# USB_Hub.net
KiCad netlist of a schematic drawn in Altium Designer
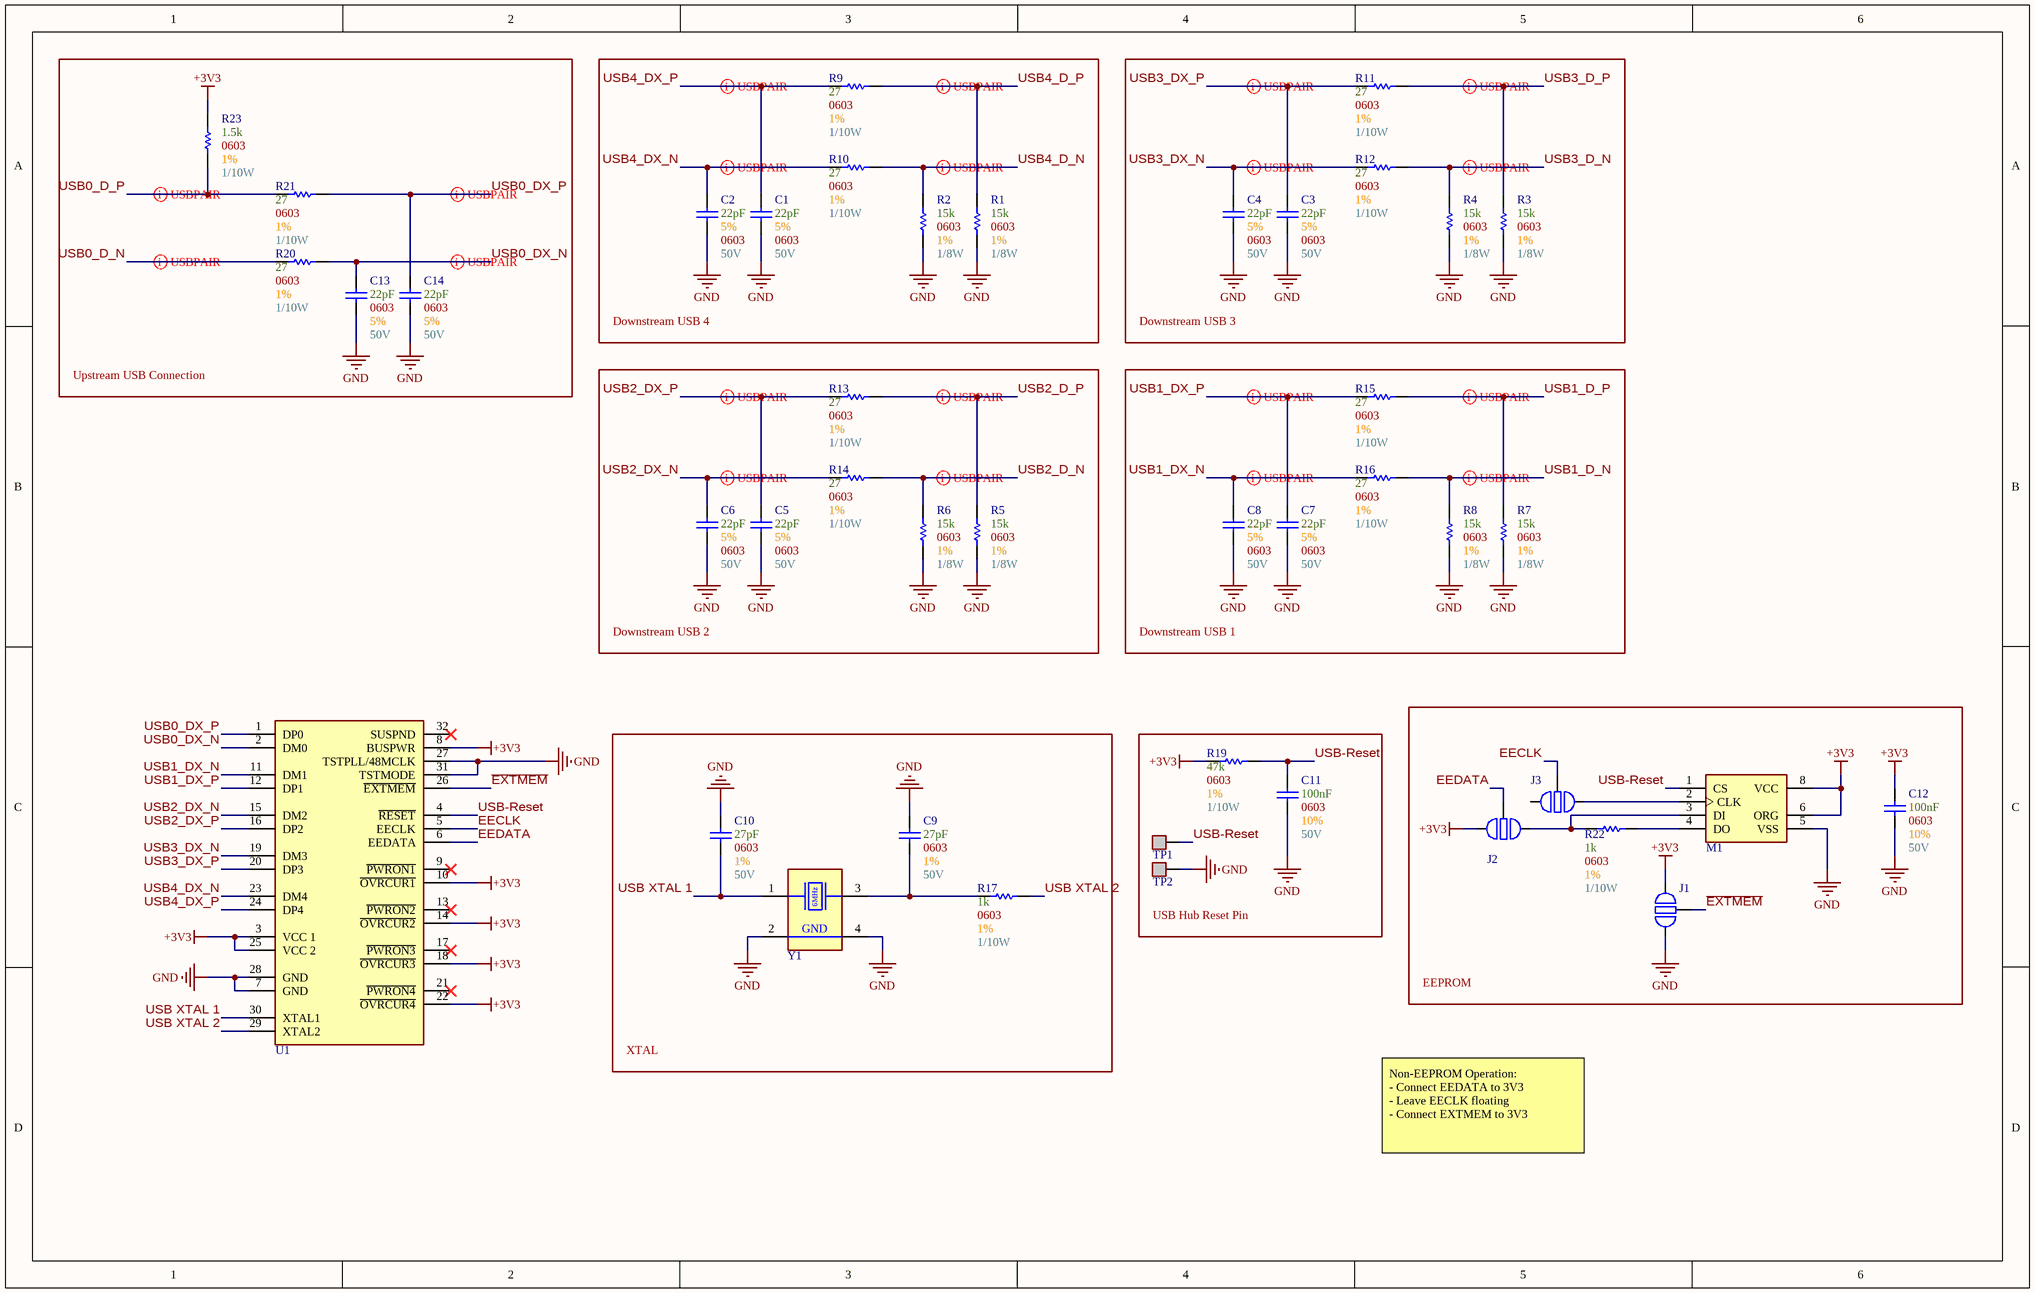
[diagram p0: USB Hub.SchDoc]

(export (version "E")
  (design (tool "Eeschema 10.0.6"))
  (components
    (comp (ref "C1")
      (value "[Cap] 0603 22pF 5% 50V")
      (footprint "[Cap] SMD 0603")
      (description "CC0603JRNPO9BN240")
      (fields
        (field (name "MAX VOLTAGE") "50V")
        (field (name "SIZE PACKAGE") "0603")
        (field (name "TOLERANCE") "5%")
        (field (name "CAPACITANCE") "22pF")
      )
      (libsource (lib "Capacitors") (part "[Cap] 0603 22pF 5% 50V"))
    )
    (comp (ref "C2")
      (value "[Cap] 0603 22pF 5% 50V")
      (footprint "[Cap] SMD 0603")
      (description "CC0603JRNPO9BN240")
      (fields
        (field (name "MAX VOLTAGE") "50V")
        (field (name "SIZE PACKAGE") "0603")
        (field (name "TOLERANCE") "5%")
        (field (name "CAPACITANCE") "22pF")
      )
      (libsource (lib "Capacitors") (part "[Cap] 0603 22pF 5% 50V"))
    )
    (comp (ref "C3")
      (value "[Cap] 0603 22pF 5% 50V")
      (footprint "[Cap] SMD 0603")
      (description "CC0603JRNPO9BN240")
      (fields
        (field (name "MAX VOLTAGE") "50V")
        (field (name "SIZE PACKAGE") "0603")
        (field (name "TOLERANCE") "5%")
        (field (name "CAPACITANCE") "22pF")
      )
      (libsource (lib "Capacitors") (part "[Cap] 0603 22pF 5% 50V"))
    )
    (comp (ref "C4")
      (value "[Cap] 0603 22pF 5% 50V")
      (footprint "[Cap] SMD 0603")
      (description "CC0603JRNPO9BN240")
      (fields
        (field (name "MAX VOLTAGE") "50V")
        (field (name "SIZE PACKAGE") "0603")
        (field (name "TOLERANCE") "5%")
        (field (name "CAPACITANCE") "22pF")
      )
      (libsource (lib "Capacitors") (part "[Cap] 0603 22pF 5% 50V"))
    )
    (comp (ref "C5")
      (value "[Cap] 0603 22pF 5% 50V")
      (footprint "[Cap] SMD 0603")
      (description "CC0603JRNPO9BN240")
      (fields
        (field (name "MAX VOLTAGE") "50V")
        (field (name "SIZE PACKAGE") "0603")
        (field (name "TOLERANCE") "5%")
        (field (name "CAPACITANCE") "22pF")
      )
      (libsource (lib "Capacitors") (part "[Cap] 0603 22pF 5% 50V"))
    )
    (comp (ref "C6")
      (value "[Cap] 0603 22pF 5% 50V")
      (footprint "[Cap] SMD 0603")
      (description "CC0603JRNPO9BN240")
      (fields
        (field (name "MAX VOLTAGE") "50V")
        (field (name "SIZE PACKAGE") "0603")
        (field (name "TOLERANCE") "5%")
        (field (name "CAPACITANCE") "22pF")
      )
      (libsource (lib "Capacitors") (part "[Cap] 0603 22pF 5% 50V"))
    )
    (comp (ref "C7")
      (value "[Cap] 0603 22pF 5% 50V")
      (footprint "[Cap] SMD 0603")
      (description "CC0603JRNPO9BN240")
      (fields
        (field (name "MAX VOLTAGE") "50V")
        (field (name "SIZE PACKAGE") "0603")
        (field (name "TOLERANCE") "5%")
        (field (name "CAPACITANCE") "22pF")
      )
      (libsource (lib "Capacitors") (part "[Cap] 0603 22pF 5% 50V"))
    )
    (comp (ref "C8")
      (value "[Cap] 0603 22pF 5% 50V")
      (footprint "[Cap] SMD 0603")
      (description "CC0603JRNPO9BN240")
      (fields
        (field (name "MAX VOLTAGE") "50V")
        (field (name "SIZE PACKAGE") "0603")
        (field (name "TOLERANCE") "5%")
        (field (name "CAPACITANCE") "22pF")
      )
      (libsource (lib "Capacitors") (part "[Cap] 0603 22pF 5% 50V"))
    )
    (comp (ref "C9")
      (value "[Cap] 0603 27pF 1% 50V")
      (footprint "[Cap] SMD 0603")
      (description "0603N270F500CT")
      (fields
        (field (name "MAX VOLTAGE") "50V")
        (field (name "SIZE PACKAGE") "0603")
        (field (name "TOLERANCE") "1%")
        (field (name "CAPACITANCE") "27pF")
      )
      (libsource (lib "Capacitors") (part "[Cap] 0603 27pF 1% 50V"))
    )
    (comp (ref "C10")
      (value "[Cap] 0603 27pF 1% 50V")
      (footprint "[Cap] SMD 0603")
      (description "0603N270F500CT")
      (fields
        (field (name "MAX VOLTAGE") "50V")
        (field (name "SIZE PACKAGE") "0603")
        (field (name "TOLERANCE") "1%")
        (field (name "CAPACITANCE") "27pF")
      )
      (libsource (lib "Capacitors") (part "[Cap] 0603 27pF 1% 50V"))
    )
    (comp (ref "C11")
      (value "[Cap] 0603 0.1uF 10% 50V")
      (footprint "[Cap] SMD 0603")
      (description "CL10B104KB8NNNC")
      (fields
        (field (name "MAX VOLTAGE") "50V")
        (field (name "SIZE PACKAGE") "0603")
        (field (name "TOLERANCE") "10%")
        (field (name "CAPACITANCE") "100nF")
      )
      (libsource (lib "Capacitors") (part "[Cap] 0603 0.1uF 10% 50V"))
    )
    (comp (ref "C12")
      (value "[Cap] 0603 0.1uF 10% 50V")
      (footprint "[Cap] SMD 0603")
      (description "CL10B104KB8NNNC")
      (fields
        (field (name "MAX VOLTAGE") "50V")
        (field (name "SIZE PACKAGE") "0603")
        (field (name "TOLERANCE") "10%")
        (field (name "CAPACITANCE") "100nF")
      )
      (libsource (lib "Capacitors") (part "[Cap] 0603 0.1uF 10% 50V"))
    )
    (comp (ref "C13")
      (value "[Cap] 0603 22pF 5% 50V")
      (footprint "[Cap] SMD 0603")
      (description "CC0603JRNPO9BN240")
      (fields
        (field (name "MAX VOLTAGE") "50V")
        (field (name "SIZE PACKAGE") "0603")
        (field (name "TOLERANCE") "5%")
        (field (name "CAPACITANCE") "22pF")
      )
      (libsource (lib "Capacitors") (part "[Cap] 0603 22pF 5% 50V"))
    )
    (comp (ref "C14")
      (value "[Cap] 0603 22pF 5% 50V")
      (footprint "[Cap] SMD 0603")
      (description "CC0603JRNPO9BN240")
      (fields
        (field (name "MAX VOLTAGE") "50V")
        (field (name "SIZE PACKAGE") "0603")
        (field (name "TOLERANCE") "5%")
        (field (name "CAPACITANCE") "22pF")
      )
      (libsource (lib "Capacitors") (part "[Cap] 0603 22pF 5% 50V"))
    )
    (comp (ref "J1")
      (value "[Jumper] Thru-Hole 3pin")
      (footprint "[Jumper] Thru-Hole 3pin")
      (libsource (lib "Misc Components") (part "[Jumper] Thru-Hole 3pin"))
    )
    (comp (ref "J2")
      (value "[Jumper] Thru-Hole 3pin")
      (footprint "[Jumper] Thru-Hole 3pin")
      (libsource (lib "Misc Components") (part "[Jumper] Thru-Hole 3pin"))
    )
    (comp (ref "J3")
      (value "[Jumper] Thru-Hole 3pin")
      (footprint "[Jumper] Thru-Hole 3pin")
      (libsource (lib "Misc Components") (part "[Jumper] Thru-Hole 3pin"))
    )
    (comp (ref "M1")
      (value "[Flash] 32x16b")
      (footprint "[Flash] 32x16b")
      (description "M93C46-WMN6TP")
      (libsource (lib "Memory") (part "[Flash] 32x16b"))
    )
    (comp (ref "R1")
      (value "[15k] SMD 0603 1% 1/8W")
      (footprint "[Res] SMD 0603")
      (description "CRCW060315K0FKEA")
      (fields
        (field (name "WATTAGE") "1/8W")
        (field (name "TOLERANCE") "1%")
        (field (name "RESISTANCE") "15k")
        (field (name "SIZE PACKAGE") "0603")
      )
      (libsource (lib "Resistors") (part "[15k] SMD 0603 1% 1/8W"))
    )
    (comp (ref "R2")
      (value "[15k] SMD 0603 1% 1/8W")
      (footprint "[Res] SMD 0603")
      (description "CRCW060315K0FKEA")
      (fields
        (field (name "WATTAGE") "1/8W")
        (field (name "TOLERANCE") "1%")
        (field (name "RESISTANCE") "15k")
        (field (name "SIZE PACKAGE") "0603")
      )
      (libsource (lib "Resistors") (part "[15k] SMD 0603 1% 1/8W"))
    )
    (comp (ref "R3")
      (value "[15k] SMD 0603 1% 1/8W")
      (footprint "[Res] SMD 0603")
      (description "CRCW060315K0FKEA")
      (fields
        (field (name "WATTAGE") "1/8W")
        (field (name "TOLERANCE") "1%")
        (field (name "RESISTANCE") "15k")
        (field (name "SIZE PACKAGE") "0603")
      )
      (libsource (lib "Resistors") (part "[15k] SMD 0603 1% 1/8W"))
    )
    (comp (ref "R4")
      (value "[15k] SMD 0603 1% 1/8W")
      (footprint "[Res] SMD 0603")
      (description "CRCW060315K0FKEA")
      (fields
        (field (name "WATTAGE") "1/8W")
        (field (name "TOLERANCE") "1%")
        (field (name "RESISTANCE") "15k")
        (field (name "SIZE PACKAGE") "0603")
      )
      (libsource (lib "Resistors") (part "[15k] SMD 0603 1% 1/8W"))
    )
    (comp (ref "R5")
      (value "[15k] SMD 0603 1% 1/8W")
      (footprint "[Res] SMD 0603")
      (description "CRCW060315K0FKEA")
      (fields
        (field (name "WATTAGE") "1/8W")
        (field (name "TOLERANCE") "1%")
        (field (name "RESISTANCE") "15k")
        (field (name "SIZE PACKAGE") "0603")
      )
      (libsource (lib "Resistors") (part "[15k] SMD 0603 1% 1/8W"))
    )
    (comp (ref "R6")
      (value "[15k] SMD 0603 1% 1/8W")
      (footprint "[Res] SMD 0603")
      (description "CRCW060315K0FKEA")
      (fields
        (field (name "WATTAGE") "1/8W")
        (field (name "TOLERANCE") "1%")
        (field (name "RESISTANCE") "15k")
        (field (name "SIZE PACKAGE") "0603")
      )
      (libsource (lib "Resistors") (part "[15k] SMD 0603 1% 1/8W"))
    )
    (comp (ref "R7")
      (value "[15k] SMD 0603 1% 1/8W")
      (footprint "[Res] SMD 0603")
      (description "CRCW060315K0FKEA")
      (fields
        (field (name "WATTAGE") "1/8W")
        (field (name "TOLERANCE") "1%")
        (field (name "RESISTANCE") "15k")
        (field (name "SIZE PACKAGE") "0603")
      )
      (libsource (lib "Resistors") (part "[15k] SMD 0603 1% 1/8W"))
    )
    (comp (ref "R8")
      (value "[15k] SMD 0603 1% 1/8W")
      (footprint "[Res] SMD 0603")
      (description "CRCW060315K0FKEA")
      (fields
        (field (name "WATTAGE") "1/8W")
        (field (name "TOLERANCE") "1%")
        (field (name "RESISTANCE") "15k")
        (field (name "SIZE PACKAGE") "0603")
      )
      (libsource (lib "Resistors") (part "[15k] SMD 0603 1% 1/8W"))
    )
    (comp (ref "R9")
      (value "[27] SMD 0603 1% 1/10W")
      (footprint "[Res] SMD 0603")
      (description "MCT06030C2709FP500")
      (fields
        (field (name "WATTAGE") "1/10W")
        (field (name "TOLERANCE") "1%")
        (field (name "RESISTANCE") "27")
        (field (name "SIZE PACKAGE") "0603")
      )
      (libsource (lib "Resistors") (part "[27] SMD 0603 1% 1/10W"))
    )
    (comp (ref "R10")
      (value "[27] SMD 0603 1% 1/10W")
      (footprint "[Res] SMD 0603")
      (description "MCT06030C2709FP500")
      (fields
        (field (name "WATTAGE") "1/10W")
        (field (name "TOLERANCE") "1%")
        (field (name "RESISTANCE") "27")
        (field (name "SIZE PACKAGE") "0603")
      )
      (libsource (lib "Resistors") (part "[27] SMD 0603 1% 1/10W"))
    )
    (comp (ref "R11")
      (value "[27] SMD 0603 1% 1/10W")
      (footprint "[Res] SMD 0603")
      (description "MCT06030C2709FP500")
      (fields
        (field (name "WATTAGE") "1/10W")
        (field (name "TOLERANCE") "1%")
        (field (name "RESISTANCE") "27")
        (field (name "SIZE PACKAGE") "0603")
      )
      (libsource (lib "Resistors") (part "[27] SMD 0603 1% 1/10W"))
    )
    (comp (ref "R12")
      (value "[27] SMD 0603 1% 1/10W")
      (footprint "[Res] SMD 0603")
      (description "MCT06030C2709FP500")
      (fields
        (field (name "WATTAGE") "1/10W")
        (field (name "TOLERANCE") "1%")
        (field (name "RESISTANCE") "27")
        (field (name "SIZE PACKAGE") "0603")
      )
      (libsource (lib "Resistors") (part "[27] SMD 0603 1% 1/10W"))
    )
    (comp (ref "R13")
      (value "[27] SMD 0603 1% 1/10W")
      (footprint "[Res] SMD 0603")
      (description "MCT06030C2709FP500")
      (fields
        (field (name "WATTAGE") "1/10W")
        (field (name "TOLERANCE") "1%")
        (field (name "RESISTANCE") "27")
        (field (name "SIZE PACKAGE") "0603")
      )
      (libsource (lib "Resistors") (part "[27] SMD 0603 1% 1/10W"))
    )
    (comp (ref "R14")
      (value "[27] SMD 0603 1% 1/10W")
      (footprint "[Res] SMD 0603")
      (description "MCT06030C2709FP500")
      (fields
        (field (name "WATTAGE") "1/10W")
        (field (name "TOLERANCE") "1%")
        (field (name "RESISTANCE") "27")
        (field (name "SIZE PACKAGE") "0603")
      )
      (libsource (lib "Resistors") (part "[27] SMD 0603 1% 1/10W"))
    )
    (comp (ref "R15")
      (value "[27] SMD 0603 1% 1/10W")
      (footprint "[Res] SMD 0603")
      (description "MCT06030C2709FP500")
      (fields
        (field (name "WATTAGE") "1/10W")
        (field (name "TOLERANCE") "1%")
        (field (name "RESISTANCE") "27")
        (field (name "SIZE PACKAGE") "0603")
      )
      (libsource (lib "Resistors") (part "[27] SMD 0603 1% 1/10W"))
    )
    (comp (ref "R16")
      (value "[27] SMD 0603 1% 1/10W")
      (footprint "[Res] SMD 0603")
      (description "MCT06030C2709FP500")
      (fields
        (field (name "WATTAGE") "1/10W")
        (field (name "TOLERANCE") "1%")
        (field (name "RESISTANCE") "27")
        (field (name "SIZE PACKAGE") "0603")
      )
      (libsource (lib "Resistors") (part "[27] SMD 0603 1% 1/10W"))
    )
    (comp (ref "R17")
      (value "[1k] SMD 0603 1% 1/10W")
      (footprint "[Res] SMD 0603")
      (description "RMCF0603FT1K00")
      (fields
        (field (name "WATTAGE") "1/10W")
        (field (name "TOLERANCE") "1%")
        (field (name "RESISTANCE") "1k")
        (field (name "SIZE PACKAGE") "0603")
      )
      (libsource (lib "Resistors") (part "[1k] SMD 0603 1% 1/10W"))
    )
    (comp (ref "R19")
      (value "[47k] SMD 0603 1% 1/10W")
      (footprint "[Res] SMD 0603")
      (description "RC0603FR-0747KL")
      (fields
        (field (name "WATTAGE") "1/10W")
        (field (name "TOLERANCE") "1%")
        (field (name "RESISTANCE") "47k")
        (field (name "SIZE PACKAGE") "0603")
      )
      (libsource (lib "Resistors") (part "[47k] SMD 0603 1% 1/10W"))
    )
    (comp (ref "R20")
      (value "[27] SMD 0603 1% 1/10W")
      (footprint "[Res] SMD 0603")
      (description "MCT06030C2709FP500")
      (fields
        (field (name "WATTAGE") "1/10W")
        (field (name "TOLERANCE") "1%")
        (field (name "RESISTANCE") "27")
        (field (name "SIZE PACKAGE") "0603")
      )
      (libsource (lib "Resistors") (part "[27] SMD 0603 1% 1/10W"))
    )
    (comp (ref "R21")
      (value "[27] SMD 0603 1% 1/10W")
      (footprint "[Res] SMD 0603")
      (description "MCT06030C2709FP500")
      (fields
        (field (name "WATTAGE") "1/10W")
        (field (name "TOLERANCE") "1%")
        (field (name "RESISTANCE") "27")
        (field (name "SIZE PACKAGE") "0603")
      )
      (libsource (lib "Resistors") (part "[27] SMD 0603 1% 1/10W"))
    )
    (comp (ref "R22")
      (value "[1k] SMD 0603 1% 1/10W")
      (footprint "[Res] SMD 0603")
      (description "RMCF0603FT1K00")
      (fields
        (field (name "WATTAGE") "1/10W")
        (field (name "TOLERANCE") "1%")
        (field (name "RESISTANCE") "1k")
        (field (name "SIZE PACKAGE") "0603")
      )
      (libsource (lib "Resistors") (part "[1k] SMD 0603 1% 1/10W"))
    )
    (comp (ref "R23")
      (value "[1.5k] SMD 0603 1% 1/10W")
      (footprint "[Res] SMD 0603")
      (description "CR0603-FX-1501ELF")
      (fields
        (field (name "WATTAGE") "1/10W")
        (field (name "TOLERANCE") "1%")
        (field (name "RESISTANCE") "1.5k")
        (field (name "SIZE PACKAGE") "0603")
      )
      (libsource (lib "Resistors") (part "[1.5k] SMD 0603 1% 1/10W"))
    )
    (comp (ref "TP1")
      (value "[THM] Thru-Hole")
      (footprint "[THM] White")
      (description "5012")
      (libsource (lib "Test Points") (part "[THM] Thru-Hole"))
    )
    (comp (ref "TP2")
      (value "[THM] Thru-Hole")
      (footprint "[THM] White")
      (description "5012")
      (libsource (lib "Test Points") (part "[THM] Thru-Hole"))
    )
    (comp (ref "U1")
      (value "4port")
      (footprint "[USB Hub] USB2.0 4port")
      (description "TUSB2046BVFR")
      (libsource (lib "ICs") (part "[USB Hub] USB 2.0 4port"))
    )
    (comp (ref "Y1")
      (value "[Crystal] SMD 6MHz")
      (footprint "[Crystal] SMD 6MHz")
      (description "ECS-060-18-20BM-JEN-TR")
      (libsource (lib "Crystals and Oscillators") (part "[Crystal] SMD 6MHz"))
    )
  )
  (nets
    (net (code "1") (name "+3V3") (class "Default")
      (node (ref "C12") (pin "2") (pinfunction "2_2") (pintype "passive"))
      (node (ref "J1") (pin "3") (pintype "passive"))
      (node (ref "J2") (pin "3") (pintype "passive"))
      (node (ref "M1") (pin "6") (pinfunction "ORG_6") (pintype "passive"))
      (node (ref "M1") (pin "8") (pinfunction "VCC_8") (pintype "passive"))
      (node (ref "R19") (pin "1") (pinfunction "1_1") (pintype "passive"))
      (node (ref "R23") (pin "2") (pinfunction "2_2") (pintype "passive"))
      (node (ref "U1") (pin "10") (pinfunction "~{OVRCUR1}_10") (pintype "passive"))
      (node (ref "U1") (pin "14") (pinfunction "~{OVRCUR2}_14") (pintype "passive"))
      (node (ref "U1") (pin "18") (pinfunction "~{OVRCUR3}_18") (pintype "passive"))
      (node (ref "U1") (pin "22") (pinfunction "~{OVRCUR4}_22") (pintype "passive"))
      (node (ref "U1") (pin "25") (pinfunction "VCC_2_25") (pintype "passive"))
      (node (ref "U1") (pin "3") (pinfunction "VCC_1_3") (pintype "passive"))
      (node (ref "U1") (pin "8") (pinfunction "BUSPWR_8") (pintype "passive"))
    )
    (net (code "2") (name "/EECLK") (class "Default")
      (node (ref "J3") (pin "2") (pinfunction "Common_2") (pintype "power_in"))
      (node (ref "U1") (pin "5") (pinfunction "EECLK_5") (pintype "passive"))
    )
    (net (code "3") (name "/EEDATA") (class "Default")
      (node (ref "J2") (pin "2") (pinfunction "Common_2") (pintype "power_in"))
      (node (ref "U1") (pin "6") (pinfunction "EEDATA_6") (pintype "passive"))
    )
    (net (code "4") (name "/EXTMEM") (class "Default")
      (node (ref "J1") (pin "2") (pinfunction "Common_2") (pintype "power_in"))
      (node (ref "U1") (pin "26") (pinfunction "~{EXTMEM}_26") (pintype "passive"))
    )
    (net (code "5") (name "/USB XTAL 1") (class "Default")
      (node (ref "C10") (pin "2") (pinfunction "2_2") (pintype "passive"))
      (node (ref "U1") (pin "30") (pinfunction "XTAL1_30") (pintype "passive"))
      (node (ref "Y1") (pin "1") (pinfunction "XTAL1_1") (pintype "power_in"))
    )
    (net (code "6") (name "/USB XTAL 2") (class "Default")
      (node (ref "R17") (pin "2") (pinfunction "2_2") (pintype "passive"))
      (node (ref "U1") (pin "29") (pinfunction "XTAL2_29") (pintype "passive"))
    )
    (net (code "7") (name "/USB-Reset") (class "Default")
      (node (ref "C11") (pin "2") (pinfunction "2_2") (pintype "passive"))
      (node (ref "M1") (pin "1") (pinfunction "CS_1") (pintype "passive"))
      (node (ref "R19") (pin "2") (pinfunction "2_2") (pintype "passive"))
      (node (ref "TP1") (pin "1") (pinfunction "1_1") (pintype "passive"))
      (node (ref "U1") (pin "4") (pinfunction "~{RESET}_4") (pintype "passive"))
    )
    (net (code "8") (name "/USB0_DX_N") (class "Default")
      (node (ref "C13") (pin "2") (pinfunction "2_2") (pintype "passive"))
      (node (ref "R20") (pin "2") (pinfunction "2_2") (pintype "passive"))
      (node (ref "U1") (pin "2") (pinfunction "DM0_2") (pintype "passive"))
    )
    (net (code "9") (name "/USB0_DX_P") (class "Default")
      (node (ref "C14") (pin "2") (pinfunction "2_2") (pintype "passive"))
      (node (ref "R21") (pin "2") (pinfunction "2_2") (pintype "passive"))
      (node (ref "U1") (pin "1") (pinfunction "DP0_1") (pintype "passive"))
    )
    (net (code "10") (name "/USB0_D_N") (class "Default")
      (node (ref "R20") (pin "1") (pinfunction "1_1") (pintype "passive"))
    )
    (net (code "11") (name "/USB0_D_P") (class "Default")
      (node (ref "R21") (pin "1") (pinfunction "1_1") (pintype "passive"))
      (node (ref "R23") (pin "1") (pinfunction "1_1") (pintype "passive"))
    )
    (net (code "12") (name "/USB1_DX_N") (class "Default")
      (node (ref "C8") (pin "2") (pinfunction "2_2") (pintype "passive"))
      (node (ref "R16") (pin "1") (pinfunction "1_1") (pintype "passive"))
      (node (ref "U1") (pin "11") (pinfunction "DM1_11") (pintype "passive"))
    )
    (net (code "13") (name "/USB1_DX_P") (class "Default")
      (node (ref "C7") (pin "2") (pinfunction "2_2") (pintype "passive"))
      (node (ref "R15") (pin "1") (pinfunction "1_1") (pintype "passive"))
      (node (ref "U1") (pin "12") (pinfunction "DP1_12") (pintype "passive"))
    )
    (net (code "14") (name "/USB1_D_N") (class "Default")
      (node (ref "R16") (pin "2") (pinfunction "2_2") (pintype "passive"))
      (node (ref "R8") (pin "2") (pinfunction "2_2") (pintype "passive"))
    )
    (net (code "15") (name "/USB1_D_P") (class "Default")
      (node (ref "R15") (pin "2") (pinfunction "2_2") (pintype "passive"))
      (node (ref "R7") (pin "2") (pinfunction "2_2") (pintype "passive"))
    )
    (net (code "16") (name "/USB2_DX_N") (class "Default")
      (node (ref "C6") (pin "2") (pinfunction "2_2") (pintype "passive"))
      (node (ref "R14") (pin "1") (pinfunction "1_1") (pintype "passive"))
      (node (ref "U1") (pin "15") (pinfunction "DM2_15") (pintype "passive"))
    )
    (net (code "17") (name "/USB2_DX_P") (class "Default")
      (node (ref "C5") (pin "2") (pinfunction "2_2") (pintype "passive"))
      (node (ref "R13") (pin "1") (pinfunction "1_1") (pintype "passive"))
      (node (ref "U1") (pin "16") (pinfunction "DP2_16") (pintype "passive"))
    )
    (net (code "18") (name "/USB2_D_N") (class "Default")
      (node (ref "R14") (pin "2") (pinfunction "2_2") (pintype "passive"))
      (node (ref "R6") (pin "2") (pinfunction "2_2") (pintype "passive"))
    )
    (net (code "19") (name "/USB2_D_P") (class "Default")
      (node (ref "R13") (pin "2") (pinfunction "2_2") (pintype "passive"))
      (node (ref "R5") (pin "2") (pinfunction "2_2") (pintype "passive"))
    )
    (net (code "20") (name "/USB3_DX_N") (class "Default")
      (node (ref "C4") (pin "2") (pinfunction "2_2") (pintype "passive"))
      (node (ref "R12") (pin "1") (pinfunction "1_1") (pintype "passive"))
      (node (ref "U1") (pin "19") (pinfunction "DM3_19") (pintype "passive"))
    )
    (net (code "21") (name "/USB3_DX_P") (class "Default")
      (node (ref "C3") (pin "2") (pinfunction "2_2") (pintype "passive"))
      (node (ref "R11") (pin "1") (pinfunction "1_1") (pintype "passive"))
      (node (ref "U1") (pin "20") (pinfunction "DP3_20") (pintype "passive"))
    )
    (net (code "22") (name "/USB3_D_N") (class "Default")
      (node (ref "R12") (pin "2") (pinfunction "2_2") (pintype "passive"))
      (node (ref "R4") (pin "2") (pinfunction "2_2") (pintype "passive"))
    )
    (net (code "23") (name "/USB3_D_P") (class "Default")
      (node (ref "R11") (pin "2") (pinfunction "2_2") (pintype "passive"))
      (node (ref "R3") (pin "2") (pinfunction "2_2") (pintype "passive"))
    )
    (net (code "24") (name "/USB4_DX_N") (class "Default")
      (node (ref "C2") (pin "2") (pinfunction "2_2") (pintype "passive"))
      (node (ref "R10") (pin "1") (pinfunction "1_1") (pintype "passive"))
      (node (ref "U1") (pin "23") (pinfunction "DM4_23") (pintype "passive"))
    )
    (net (code "25") (name "/USB4_DX_P") (class "Default")
      (node (ref "C1") (pin "2") (pinfunction "2_2") (pintype "passive"))
      (node (ref "R9") (pin "1") (pinfunction "1_1") (pintype "passive"))
      (node (ref "U1") (pin "24") (pinfunction "DP4_24") (pintype "passive"))
    )
    (net (code "26") (name "/USB4_D_N") (class "Default")
      (node (ref "R10") (pin "2") (pinfunction "2_2") (pintype "passive"))
      (node (ref "R2") (pin "2") (pinfunction "2_2") (pintype "passive"))
    )
    (net (code "27") (name "/USB4_D_P") (class "Default")
      (node (ref "R1") (pin "2") (pinfunction "2_2") (pintype "passive"))
      (node (ref "R9") (pin "2") (pinfunction "2_2") (pintype "passive"))
    )
    (net (code "28") (name "GND") (class "Default")
      (node (ref "C1") (pin "1") (pinfunction "1_1") (pintype "passive"))
      (node (ref "C10") (pin "1") (pinfunction "1_1") (pintype "passive"))
      (node (ref "C11") (pin "1") (pinfunction "1_1") (pintype "passive"))
      (node (ref "C12") (pin "1") (pinfunction "1_1") (pintype "passive"))
      (node (ref "C13") (pin "1") (pinfunction "1_1") (pintype "passive"))
      (node (ref "C14") (pin "1") (pinfunction "1_1") (pintype "passive"))
      (node (ref "C2") (pin "1") (pinfunction "1_1") (pintype "passive"))
      (node (ref "C3") (pin "1") (pinfunction "1_1") (pintype "passive"))
      (node (ref "C4") (pin "1") (pinfunction "1_1") (pintype "passive"))
      (node (ref "C5") (pin "1") (pinfunction "1_1") (pintype "passive"))
      (node (ref "C6") (pin "1") (pinfunction "1_1") (pintype "passive"))
      (node (ref "C7") (pin "1") (pinfunction "1_1") (pintype "passive"))
      (node (ref "C8") (pin "1") (pinfunction "1_1") (pintype "passive"))
      (node (ref "C9") (pin "1") (pinfunction "1_1") (pintype "passive"))
      (node (ref "J1") (pin "1") (pintype "passive"))
      (node (ref "M1") (pin "5") (pinfunction "VSS_5") (pintype "passive"))
      (node (ref "R1") (pin "1") (pinfunction "1_1") (pintype "passive"))
      (node (ref "R2") (pin "1") (pinfunction "1_1") (pintype "passive"))
      (node (ref "R3") (pin "1") (pinfunction "1_1") (pintype "passive"))
      (node (ref "R4") (pin "1") (pinfunction "1_1") (pintype "passive"))
      (node (ref "R5") (pin "1") (pinfunction "1_1") (pintype "passive"))
      (node (ref "R6") (pin "1") (pinfunction "1_1") (pintype "passive"))
      (node (ref "R7") (pin "1") (pinfunction "1_1") (pintype "passive"))
      (node (ref "R8") (pin "1") (pinfunction "1_1") (pintype "passive"))
      (node (ref "TP2") (pin "1") (pinfunction "1_1") (pintype "passive"))
      (node (ref "U1") (pin "27") (pinfunction "TSTPLL/48MCLK_27") (pintype "passive"))
      (node (ref "U1") (pin "28") (pinfunction "GND_28") (pintype "passive"))
      (node (ref "U1") (pin "31") (pinfunction "TSTMODE_31") (pintype "passive"))
      (node (ref "U1") (pin "7") (pinfunction "GND_7") (pintype "passive"))
      (node (ref "Y1") (pin "2") (pinfunction "GND_2") (pintype "power_in"))
      (node (ref "Y1") (pin "4") (pinfunction "GND_4") (pintype "power_in"))
    )
    (net (code "29") (name "Net-(M1-CLK)") (class "Default")
      (node (ref "J3") (pin "1") (pintype "passive"))
      (node (ref "M1") (pin "2") (pinfunction "CLK_2") (pintype "passive"))
    )
    (net (code "30") (name "Net-(M1-DI)") (class "Default")
      (node (ref "J2") (pin "1") (pintype "passive"))
      (node (ref "M1") (pin "3") (pinfunction "DI_3") (pintype "passive"))
      (node (ref "R22") (pin "2") (pinfunction "2_2") (pintype "passive"))
    )
    (net (code "31") (name "Net-(M1-DO)") (class "Default")
      (node (ref "M1") (pin "4") (pinfunction "DO_4") (pintype "passive"))
      (node (ref "R22") (pin "1") (pinfunction "1_1") (pintype "passive"))
    )
    (net (code "32") (name "Net-(Y1-XTAL2)") (class "Default")
      (node (ref "C9") (pin "2") (pinfunction "2_2") (pintype "passive"))
      (node (ref "R17") (pin "1") (pinfunction "1_1") (pintype "passive"))
      (node (ref "Y1") (pin "3") (pinfunction "XTAL2_3") (pintype "power_in"))
    )
    (net (code "33") (name "unconnected-(J3-Pad3)") (class "Default")
      (node (ref "J3") (pin "3") (pintype "passive"))
    )
    (net (code "34") (name "unconnected-(U1-SUSPND-Pad32)") (class "Default")
      (node (ref "U1") (pin "32") (pinfunction "SUSPND_32") (pintype "passive+no_connect"))
    )
    (net (code "35") (name "unconnected-(U1-~{PWRON1}-Pad9)") (class "Default")
      (node (ref "U1") (pin "9") (pinfunction "~{PWRON1}_9") (pintype "passive+no_connect"))
    )
    (net (code "36") (name "unconnected-(U1-~{PWRON2}-Pad13)") (class "Default")
      (node (ref "U1") (pin "13") (pinfunction "~{PWRON2}_13") (pintype "passive+no_connect"))
    )
    (net (code "37") (name "unconnected-(U1-~{PWRON3}-Pad17)") (class "Default")
      (node (ref "U1") (pin "17") (pinfunction "~{PWRON3}_17") (pintype "passive+no_connect"))
    )
    (net (code "38") (name "unconnected-(U1-~{PWRON4}-Pad21)") (class "Default")
      (node (ref "U1") (pin "21") (pinfunction "~{PWRON4}_21") (pintype "passive+no_connect"))
    )
  )
)
